# ST_LINK_V2.net
KiCad netlist of a schematic drawn in Altium Designer
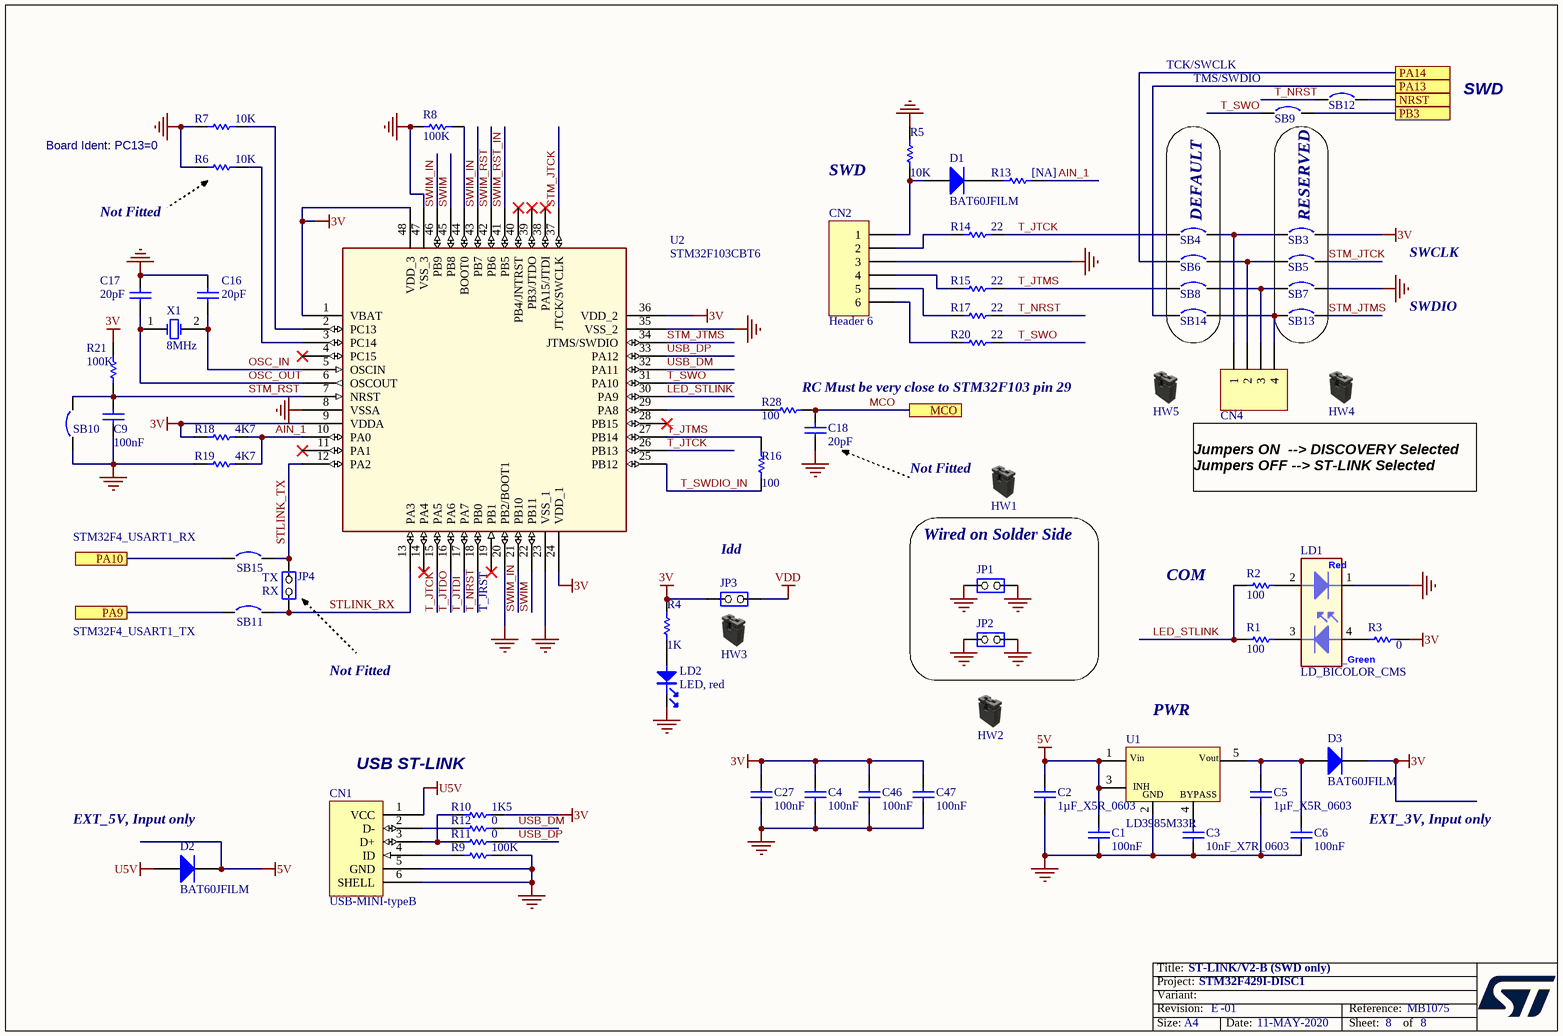
[diagram p0: ST_LINK_V2.SCHDOC]

(export (version "E")
  (design (tool "Eeschema 10.0.6"))
  (components
    (comp (ref "C1")
      (value "100nF")
      (footprint "0402C")
      (description "Capacitor 0402 / 0603 / 0805")
      (libsource (lib "MCD_TOOLS") (part "Capacitor_ST"))
    )
    (comp (ref "C2")
      (value "1µF_X5R_0603")
      (footprint "0603C")
      (description "0603  X5R 1µF")
      (fields (field (name "TOLERANCE") "10%"))
      (libsource (lib "MB963_1") (part "CAP SMD 0603  X5R 1µF 25V 10%"))
    )
    (comp (ref "C3")
      (value "10nF_X7R_0603")
      (footprint "0603C")
      (description "0603  X7R 10NF")
      (fields (field (name "TOLERANCE") "10%"))
      (libsource (lib "MB963_1") (part "CAP SMD 0603  X7R 10000PF 50V 10%"))
    )
    (comp (ref "C4")
      (value "100nF")
      (footprint "0402C")
      (description "Capacitor 0402 / 0603 / 0805")
      (libsource (lib "MCD_TOOLS") (part "Capacitor_ST"))
    )
    (comp (ref "C5")
      (value "1µF_X5R_0603")
      (footprint "0603C")
      (description "0603  X5R 1µF")
      (fields (field (name "TOLERANCE") "10%"))
      (libsource (lib "MB963_1") (part "CAP SMD 0603  X5R 1µF 25V 10%"))
    )
    (comp (ref "C6")
      (value "100nF")
      (footprint "0402C")
      (description "Capacitor 0402 / 0603 / 0805")
      (libsource (lib "MCD_TOOLS") (part "Capacitor_ST"))
    )
    (comp (ref "C9")
      (value "100nF")
      (footprint "0402C")
      (description "Capacitor 0402 / 0603 / 0805")
      (libsource (lib "MCD_TOOLS") (part "Capacitor_ST"))
    )
    (comp (ref "C16")
      (value "20pF")
      (footprint "0402C")
      (description "Capacitor 0402 / 0603 / 0805")
      (libsource (lib "MCD_TOOLS") (part "Capacitor_ST"))
    )
    (comp (ref "C17")
      (value "20pF")
      (footprint "0402C")
      (description "Capacitor 0402 / 0603 / 0805")
      (libsource (lib "MCD_TOOLS") (part "Capacitor_ST"))
    )
    (comp (ref "C18")
      (value "20pF")
      (footprint "0402C")
      (description "Capacitor 0402 / 0603 / 0805")
      (libsource (lib "MCD_TOOLS") (part "Capacitor_ST"))
    )
    (comp (ref "C27")
      (value "100nF")
      (footprint "0402C")
      (description "Capacitor 0402 / 0603 / 0805")
      (libsource (lib "MCD_TOOLS") (part "Capacitor_ST"))
    )
    (comp (ref "C46")
      (value "100nF")
      (footprint "0402C")
      (description "Capacitor 0402 / 0603 / 0805")
      (libsource (lib "MCD_TOOLS") (part "Capacitor_ST"))
    )
    (comp (ref "C47")
      (value "100nF")
      (footprint "0402C")
      (description "Capacitor 0402 / 0603 / 0805")
      (libsource (lib "MCD_TOOLS") (part "Capacitor_ST"))
    )
    (comp (ref "CN1")
      (value "USB-MINI-typeB")
      (footprint "USB-MINI-B-SMD")
      (description "USB-MINI-typeB connector")
      (libsource (lib "MCD_TOOLS") (part "USB-MINI-typeB connector"))
    )
    (comp (ref "CN2")
      (value "Header 6")
      (footprint "HDR1X6")
      (description "Header, 6-Pin")
      (fields (field (name "PUBLISHER") "Altium Limited"))
      (libsource (lib "Miscellaneous Connectors") (part "Header 6"))
    )
    (comp (ref "CN4")
      (value "Header 4")
      (footprint "Header 4")
      (description "Header, 4-Pin")
      (fields (field (name "PUBLISHER") "Altium Limited"))
      (libsource (lib "MB963_1") (part "Header 4"))
    )
    (comp (ref "D1")
      (value "BAT60JFILM")
      (footprint "SOD323/A")
      (libsource (lib "MCD_TOOLS") (part "BAT60JFILM"))
    )
    (comp (ref "D2")
      (value "BAT60JFILM")
      (footprint "SOD323/A")
      (libsource (lib "MCD_TOOLS") (part "BAT60JFILM"))
    )
    (comp (ref "D3")
      (value "BAT60JFILM")
      (footprint "SOD323/A")
      (libsource (lib "MCD_TOOLS") (part "BAT60JFILM"))
    )
    (comp (ref "HW1") (value "Shunt Black 2.54mm") (libsource (lib "MB1075") (part "Shunt Black 2.54mm")))
    (comp (ref "HW2") (value "Shunt Black 2.54mm") (libsource (lib "MB1075") (part "Shunt Black 2.54mm")))
    (comp (ref "HW3") (value "Shunt Black 2.54mm") (libsource (lib "MB1075") (part "Shunt Black 2.54mm")))
    (comp (ref "HW4") (value "Shunt Black 2.54mm") (libsource (lib "MB1075") (part "Shunt Black 2.54mm")))
    (comp (ref "HW5") (value "Shunt Black 2.54mm") (libsource (lib "MB1075") (part "Shunt Black 2.54mm")))
    (comp (ref "JP1") (value "~") (footprint "SIP2/2.54") (libsource (lib "*") (part "JP2")))
    (comp (ref "JP2") (value "~") (footprint "SIP2/2.54") (libsource (lib "*") (part "JP2")))
    (comp (ref "JP3") (value "~") (footprint "SIP2/2.54") (libsource (lib "*") (part "JP2")))
    (comp (ref "JP4") (value "JP2") (footprint "SIP2/2.54") (libsource (lib "MCD_TOOLS") (part "JP2")))
    (comp (ref "LD1")
      (value "LD_BICOLOR_CMS")
      (footprint "HSMF-A201")
      (description "Bicolor Led")
      (libsource (lib "MCD_TOOLS") (part "LD_BICOLOR_CMS"))
    )
    (comp (ref "LD2")
      (value "LED, red")
      (footprint "0603D")
      (description "LED, red, 0603")
      (libsource (lib "MCD_TOOLS") (part "LED_red"))
    )
    (comp (ref "R1")
      (value "100")
      (footprint "0402R")
      (description "Resistor 0402 / 0603 / 0805")
      (libsource (lib "MCD_TOOLS") (part "Resistor_ST"))
    )
    (comp (ref "R2")
      (value "100")
      (footprint "0402R")
      (description "Resistor 0402 / 0603 / 0805")
      (libsource (lib "MCD_TOOLS") (part "Resistor_ST"))
    )
    (comp (ref "R3")
      (value "0")
      (footprint "0402R")
      (description "Resistor 0402 / 0603 / 0805")
      (libsource (lib "MCD_TOOLS") (part "Resistor_ST"))
    )
    (comp (ref "R4")
      (value "1K")
      (footprint "0402R")
      (description "Resistor 0402 / 0603 / 0805")
      (libsource (lib "MCD_TOOLS") (part "Resistor_ST"))
    )
    (comp (ref "R5")
      (value "10K")
      (footprint "0402R")
      (description "Resistor 0402 / 0603 / 0805")
      (libsource (lib "MCD_TOOLS") (part "Resistor_ST"))
    )
    (comp (ref "R6")
      (value "10K")
      (footprint "0402R")
      (description "Resistor 0402 / 0603 / 0805")
      (libsource (lib "MCD_TOOLS") (part "Resistor_ST"))
    )
    (comp (ref "R7")
      (value "10K")
      (footprint "0402R")
      (description "Resistor 0402 / 0603 / 0805")
      (libsource (lib "MCD_TOOLS") (part "Resistor_ST"))
    )
    (comp (ref "R8")
      (value "100K")
      (footprint "0402R")
      (description "Resistor 0402 / 0603 / 0805")
      (libsource (lib "MCD_TOOLS") (part "Resistor_ST"))
    )
    (comp (ref "R9")
      (value "100K")
      (footprint "0402R")
      (description "Resistor 0402 / 0603 / 0805")
      (libsource (lib "MCD_TOOLS") (part "Resistor_ST"))
    )
    (comp (ref "R10")
      (value "1K5")
      (footprint "0402R")
      (description "Resistor 0402 / 0603 / 0805")
      (libsource (lib "MCD_TOOLS") (part "Resistor_ST"))
    )
    (comp (ref "R11")
      (value "0")
      (footprint "0402R")
      (description "Resistor 0402 / 0603 / 0805")
      (libsource (lib "MCD_TOOLS") (part "Resistor_ST"))
    )
    (comp (ref "R12")
      (value "0")
      (footprint "0402R")
      (description "Resistor 0402 / 0603 / 0805")
      (libsource (lib "MCD_TOOLS") (part "Resistor_ST"))
    )
    (comp (ref "R13")
      (value "[NA]")
      (footprint "0402R")
      (description "Resistor 0402 / 0603 / 0805")
      (libsource (lib "MCD_TOOLS") (part "Resistor_ST"))
    )
    (comp (ref "R14")
      (value "22")
      (footprint "0402R")
      (description "Resistor 0402 / 0603 / 0805")
      (libsource (lib "MCD_TOOLS") (part "Resistor_ST"))
    )
    (comp (ref "R15")
      (value "22")
      (footprint "0402R")
      (description "Resistor 0402 / 0603 / 0805")
      (libsource (lib "MCD_TOOLS") (part "Resistor_ST"))
    )
    (comp (ref "R16")
      (value "100")
      (footprint "0402R")
      (description "Resistor 0402 / 0603 / 0805")
      (libsource (lib "MCD_TOOLS") (part "Resistor_ST"))
    )
    (comp (ref "R17")
      (value "22")
      (footprint "0402R")
      (description "Resistor 0402 / 0603 / 0805")
      (libsource (lib "MCD_TOOLS") (part "Resistor_ST"))
    )
    (comp (ref "R18")
      (value "4K7")
      (footprint "0402R")
      (description "Resistor 0402 / 0603 / 0805")
      (libsource (lib "MCD_TOOLS") (part "Resistor_ST"))
    )
    (comp (ref "R19")
      (value "4K7")
      (footprint "0402R")
      (description "Resistor 0402 / 0603 / 0805")
      (libsource (lib "MCD_TOOLS") (part "Resistor_ST"))
    )
    (comp (ref "R20")
      (value "22")
      (footprint "0402R")
      (description "Resistor 0402 / 0603 / 0805")
      (libsource (lib "MCD_TOOLS") (part "Resistor_ST"))
    )
    (comp (ref "R21")
      (value "100K")
      (footprint "0402R")
      (description "Resistor 0402 / 0603 / 0805")
      (libsource (lib "MCD_TOOLS") (part "Resistor_ST"))
    )
    (comp (ref "R28")
      (value "100")
      (footprint "0402R")
      (description "Resistor 0402 / 0603 / 0805")
      (libsource (lib "MCD_TOOLS") (part "Resistor_ST"))
    )
    (comp (ref "SB3")
      (value "Circuit Breaker")
      (footprint "JP2_SMD")
      (fields (field (name "PUBLISHER") "Altium Limited"))
      (libsource (lib "MB915") (part "Circuit Breaker"))
    )
    (comp (ref "SB4")
      (value "Circuit Breaker")
      (footprint "JP2_SMD")
      (fields (field (name "PUBLISHER") "Altium Limited"))
      (libsource (lib "MB915") (part "Circuit Breaker"))
    )
    (comp (ref "SB5")
      (value "Circuit Breaker")
      (footprint "JP2_SMD")
      (fields (field (name "PUBLISHER") "Altium Limited"))
      (libsource (lib "MB915") (part "Circuit Breaker"))
    )
    (comp (ref "SB6")
      (value "Circuit Breaker")
      (footprint "JP2_SMD")
      (fields (field (name "PUBLISHER") "Altium Limited"))
      (libsource (lib "MB915") (part "Circuit Breaker"))
    )
    (comp (ref "SB7")
      (value "Circuit Breaker")
      (footprint "JP2_SMD")
      (fields (field (name "PUBLISHER") "Altium Limited"))
      (libsource (lib "MB915") (part "Circuit Breaker"))
    )
    (comp (ref "SB8")
      (value "Circuit Breaker")
      (footprint "JP2_SMD")
      (fields (field (name "PUBLISHER") "Altium Limited"))
      (libsource (lib "MB915") (part "Circuit Breaker"))
    )
    (comp (ref "SB9")
      (value "Circuit Breaker")
      (footprint "JP2_SMD")
      (fields (field (name "PUBLISHER") "Altium Limited"))
      (libsource (lib "MCD_TOOLS") (part "Circuit Breaker"))
    )
    (comp (ref "SB10")
      (value "Circuit Breaker")
      (footprint "JP2_SMD")
      (fields (field (name "PUBLISHER") "Altium Limited"))
      (libsource (lib "MB915") (part "Circuit Breaker"))
    )
    (comp (ref "SB11")
      (value "Circuit Breaker")
      (footprint "JP2_SMD")
      (fields (field (name "PUBLISHER") "Altium Limited"))
      (libsource (lib "MCD_TOOLS") (part "Circuit Breaker"))
    )
    (comp (ref "SB12")
      (value "Circuit Breaker")
      (footprint "JP2_SMD")
      (fields (field (name "PUBLISHER") "Altium Limited"))
      (libsource (lib "MB915") (part "Circuit Breaker"))
    )
    (comp (ref "SB13")
      (value "Circuit Breaker")
      (footprint "JP2_SMD")
      (fields (field (name "PUBLISHER") "Altium Limited"))
      (libsource (lib "MB915") (part "Circuit Breaker"))
    )
    (comp (ref "SB14")
      (value "Circuit Breaker")
      (footprint "JP2_SMD")
      (fields (field (name "PUBLISHER") "Altium Limited"))
      (libsource (lib "MB915") (part "Circuit Breaker"))
    )
    (comp (ref "SB15")
      (value "Circuit Breaker")
      (footprint "JP2_SMD")
      (fields (field (name "PUBLISHER") "Altium Limited"))
      (libsource (lib "MCD_TOOLS") (part "Circuit Breaker"))
    )
    (comp (ref "U1")
      (value "LD3985M33R")
      (footprint "SOT-23-5L")
      (description "Ultra low drop-low noise BiCMOS voltage, regulators low ESR capacitors compatible")
      (libsource (lib "MCD_TOOLS") (part "LD3985M33R"))
    )
    (comp (ref "U2")
      (value "STM32F103CBT6")
      (footprint "QFP48 7x7")
      (description "Medium-density performance line ARM-based 32-bit MCU with 128KB Flash")
      (libsource (lib "MCD_TOOLS") (part "STM32F103CBT6"))
    )
    (comp (ref "X1")
      (value "8MHz")
      (footprint "XTAL1")
      (description "Crystal Oscillator,8Mhz,20PF,20PPM,-10-70 degree,DIP,HC-49S")
      (libsource (lib "MCD_TOOLS") (part "XTAL"))
    )
  )
  (nets
    (net (code "1") (name "/AIN_1") (class "Default")
      (node (ref "R13") (pin "2") (pinfunction "2_2") (pintype "passive"))
      (node (ref "R18") (pin "2") (pinfunction "2_2") (pintype "passive"))
      (node (ref "R19") (pin "2") (pinfunction "2_2") (pintype "passive"))
      (node (ref "U2") (pin "10") (pinfunction "PA0_10") (pintype "bidirectional"))
    )
    (net (code "2") (name "/LED_STLINK") (class "Default")
      (node (ref "R1") (pin "1") (pinfunction "1_1") (pintype "passive"))
      (node (ref "R2") (pin "1") (pinfunction "1_1") (pintype "passive"))
      (node (ref "U2") (pin "30") (pinfunction "PA9_30") (pintype "bidirectional"))
    )
    (net (code "3") (name "/MCO") (class "Default")
      (node (ref "C18") (pin "2") (pinfunction "2_2") (pintype "passive"))
      (node (ref "R28") (pin "2") (pinfunction "2_2") (pintype "passive"))
    )
    (net (code "4") (name "/NRST") (class "Default")
      (node (ref "SB12") (pin "2") (pinfunction "2_2") (pintype "passive"))
    )
    (net (code "5") (name "/OSC_IN") (class "Default")
      (node (ref "C16") (pin "1") (pinfunction "1_1") (pintype "passive"))
      (node (ref "U2") (pin "5") (pinfunction "OSCIN_5") (pintype "input"))
      (node (ref "X1") (pin "2") (pinfunction "OSC2_2") (pintype "passive"))
    )
    (net (code "6") (name "/OSC_OUT") (class "Default")
      (node (ref "C17") (pin "1") (pinfunction "1_1") (pintype "passive"))
      (node (ref "U2") (pin "6") (pinfunction "OSCOUT_6") (pintype "output"))
      (node (ref "X1") (pin "1") (pinfunction "OSC1_1") (pintype "passive"))
    )
    (net (code "7") (name "/PA9") (class "Default")
      (node (ref "SB11") (pin "1") (pinfunction "1_1") (pintype "passive"))
    )
    (net (code "8") (name "/PA10") (class "Default")
      (node (ref "SB15") (pin "1") (pinfunction "1_1") (pintype "passive"))
    )
    (net (code "9") (name "/PA13") (class "Default")
      (node (ref "SB14") (pin "1") (pinfunction "1_1") (pintype "passive"))
    )
    (net (code "10") (name "/PA14") (class "Default")
      (node (ref "SB6") (pin "1") (pinfunction "1_1") (pintype "passive"))
    )
    (net (code "11") (name "/PB3") (class "Default")
      (node (ref "SB9") (pin "2") (pinfunction "2_2") (pintype "passive"))
    )
    (net (code "12") (name "/STLINK_RX") (class "Default")
      (node (ref "JP4") (pin "1") (pinfunction "COMMON_1") (pintype "passive"))
      (node (ref "SB11") (pin "2") (pinfunction "2_2") (pintype "passive"))
      (node (ref "U2") (pin "13") (pinfunction "PA3_13") (pintype "bidirectional"))
    )
    (net (code "13") (name "/STLINK_TX") (class "Default")
      (node (ref "JP4") (pin "2") (pinfunction "NO_2") (pintype "passive"))
      (node (ref "SB15") (pin "2") (pinfunction "2_2") (pintype "passive"))
      (node (ref "U2") (pin "12") (pinfunction "PA2_12") (pintype "bidirectional"))
    )
    (net (code "14") (name "/STM_JTCK") (class "Default")
      (node (ref "SB5") (pin "2") (pinfunction "2_2") (pintype "passive"))
      (node (ref "U2") (pin "37") (pinfunction "JTCK/SWCLK_37") (pintype "bidirectional"))
    )
    (net (code "15") (name "/STM_JTMS") (class "Default")
      (node (ref "SB13") (pin "2") (pinfunction "2_2") (pintype "passive"))
      (node (ref "U2") (pin "34") (pinfunction "JTMS/SWDIO_34") (pintype "bidirectional"))
    )
    (net (code "16") (name "/STM_RST") (class "Default")
      (node (ref "C9") (pin "2") (pinfunction "2_2") (pintype "passive"))
      (node (ref "R21") (pin "1") (pinfunction "1_1") (pintype "passive"))
      (node (ref "SB10") (pin "2") (pinfunction "2_2") (pintype "passive"))
      (node (ref "U2") (pin "7") (pinfunction "NRST_7") (pintype "input"))
    )
    (net (code "17") (name "/SWIM") (class "Default")
      (node (ref "U2") (pin "22") (pinfunction "PB11_22") (pintype "bidirectional"))
      (node (ref "U2") (pin "45") (pinfunction "PB8_45") (pintype "bidirectional"))
    )
    (net (code "18") (name "/SWIM_IN") (class "Default")
      (node (ref "U2") (pin "21") (pinfunction "PB10_21") (pintype "bidirectional"))
      (node (ref "U2") (pin "43") (pinfunction "PB7_43") (pintype "bidirectional"))
      (node (ref "U2") (pin "46") (pinfunction "PB9_46") (pintype "bidirectional"))
    )
    (net (code "19") (name "/SWIM_RST") (class "Default")
      (node (ref "U2") (pin "42") (pinfunction "PB6_42") (pintype "bidirectional"))
    )
    (net (code "20") (name "/SWIM_RST_IN") (class "Default")
      (node (ref "U2") (pin "41") (pinfunction "PB5_41") (pintype "bidirectional"))
    )
    (net (code "21") (name "/T_JTCK") (class "Default")
      (node (ref "R14") (pin "2") (pinfunction "2_2") (pintype "passive"))
      (node (ref "SB4") (pin "1") (pinfunction "1_1") (pintype "passive"))
      (node (ref "U2") (pin "15") (pinfunction "PA5_15") (pintype "bidirectional"))
      (node (ref "U2") (pin "26") (pinfunction "PB13_26") (pintype "bidirectional"))
    )
    (net (code "22") (name "/T_JTDI") (class "Default")
      (node (ref "U2") (pin "17") (pinfunction "PA7_17") (pintype "bidirectional"))
    )
    (net (code "23") (name "/T_JTDO") (class "Default")
      (node (ref "U2") (pin "16") (pinfunction "PA6_16") (pintype "bidirectional"))
    )
    (net (code "24") (name "/T_JTMS") (class "Default")
      (node (ref "R15") (pin "2") (pinfunction "2_2") (pintype "passive"))
      (node (ref "R16") (pin "2") (pinfunction "2_2") (pintype "passive"))
      (node (ref "SB8") (pin "1") (pinfunction "1_1") (pintype "passive"))
      (node (ref "U2") (pin "27") (pinfunction "PB14_27") (pintype "bidirectional"))
    )
    (net (code "25") (name "/T_NRST") (class "Default")
      (node (ref "R17") (pin "2") (pinfunction "2_2") (pintype "passive"))
      (node (ref "SB12") (pin "1") (pinfunction "1_1") (pintype "passive"))
      (node (ref "U2") (pin "18") (pinfunction "PB0_18") (pintype "bidirectional"))
    )
    (net (code "26") (name "/T_SWDIO_IN") (class "Default")
      (node (ref "R16") (pin "1") (pinfunction "1_1") (pintype "passive"))
      (node (ref "U2") (pin "25") (pinfunction "PB12_25") (pintype "bidirectional"))
    )
    (net (code "27") (name "/T_SWO") (class "Default")
      (node (ref "R20") (pin "2") (pinfunction "2_2") (pintype "passive"))
      (node (ref "SB9") (pin "1") (pinfunction "1_1") (pintype "passive"))
      (node (ref "U2") (pin "31") (pinfunction "PA10_31") (pintype "bidirectional"))
    )
    (net (code "28") (name "/USB_DM") (class "Default")
      (node (ref "R12") (pin "2") (pinfunction "2_2") (pintype "passive"))
      (node (ref "U2") (pin "32") (pinfunction "PA11_32") (pintype "bidirectional"))
    )
    (net (code "29") (name "/USB_DP") (class "Default")
      (node (ref "R11") (pin "2") (pinfunction "2_2") (pintype "passive"))
      (node (ref "U2") (pin "33") (pinfunction "PA12_33") (pintype "bidirectional"))
    )
    (net (code "30") (name "3V") (class "Default")
      (node (ref "C27") (pin "2") (pinfunction "2_2") (pintype "passive"))
      (node (ref "C4") (pin "2") (pinfunction "2_2") (pintype "passive"))
      (node (ref "C46") (pin "2") (pinfunction "2_2") (pintype "passive"))
      (node (ref "C47") (pin "2") (pinfunction "2_2") (pintype "passive"))
      (node (ref "D3") (pin "2") (pinfunction "K_2") (pintype "passive"))
      (node (ref "JP3") (pin "1") (pinfunction "COMMON_1") (pintype "passive"))
      (node (ref "R10") (pin "2") (pinfunction "2_2") (pintype "passive"))
      (node (ref "R18") (pin "1") (pinfunction "1_1") (pintype "passive"))
      (node (ref "R21") (pin "2") (pinfunction "2_2") (pintype "passive"))
      (node (ref "R3") (pin "2") (pinfunction "2_2") (pintype "passive"))
      (node (ref "R4") (pin "2") (pinfunction "2_2") (pintype "passive"))
      (node (ref "SB3") (pin "2") (pinfunction "2_2") (pintype "passive"))
      (node (ref "U2") (pin "1") (pinfunction "VBAT_1") (pintype "power_in"))
      (node (ref "U2") (pin "24") (pinfunction "VDD_1_24") (pintype "power_in"))
      (node (ref "U2") (pin "36") (pinfunction "VDD_2_36") (pintype "power_in"))
      (node (ref "U2") (pin "48") (pinfunction "VDD_3_48") (pintype "power_in"))
      (node (ref "U2") (pin "9") (pinfunction "VDDA_9") (pintype "power_in"))
    )
    (net (code "31") (name "5V") (class "Default")
      (node (ref "C1") (pin "2") (pinfunction "2_2") (pintype "passive"))
      (node (ref "C2") (pin "2") (pinfunction "2_2") (pintype "passive"))
      (node (ref "D2") (pin "2") (pinfunction "K_2") (pintype "passive"))
      (node (ref "U1") (pin "1") (pinfunction "Vin_1") (pintype "passive"))
      (node (ref "U1") (pin "3") (pinfunction "CE_3") (pintype "passive"))
    )
    (net (code "32") (name "GND") (class "Default")
      (node (ref "C1") (pin "1") (pinfunction "1_1") (pintype "passive"))
      (node (ref "C16") (pin "2") (pinfunction "2_2") (pintype "passive"))
      (node (ref "C17") (pin "2") (pinfunction "2_2") (pintype "passive"))
      (node (ref "C18") (pin "1") (pinfunction "1_1") (pintype "passive"))
      (node (ref "C2") (pin "1") (pinfunction "1_1") (pintype "passive"))
      (node (ref "C27") (pin "1") (pinfunction "1_1") (pintype "passive"))
      (node (ref "C3") (pin "1") (pinfunction "1_1") (pintype "passive"))
      (node (ref "C4") (pin "1") (pinfunction "1_1") (pintype "passive"))
      (node (ref "C46") (pin "1") (pinfunction "1_1") (pintype "passive"))
      (node (ref "C47") (pin "1") (pinfunction "1_1") (pintype "passive"))
      (node (ref "C5") (pin "2") (pinfunction "2_2") (pintype "passive"))
      (node (ref "C6") (pin "1") (pinfunction "1_1") (pintype "passive"))
      (node (ref "C9") (pin "1") (pinfunction "1_1") (pintype "passive"))
      (node (ref "CN1") (pin "5") (pinfunction "GND_5") (pintype "passive"))
      (node (ref "CN1") (pin "6") (pinfunction "SHELL_6") (pintype "passive"))
      (node (ref "CN2") (pin "3") (pinfunction "3_3") (pintype "passive"))
      (node (ref "JP1") (pin "1") (pinfunction "COMMON_1") (pintype "passive"))
      (node (ref "JP1") (pin "2") (pinfunction "NO_2") (pintype "passive"))
      (node (ref "JP2") (pin "1") (pinfunction "COMMON_1") (pintype "passive"))
      (node (ref "JP2") (pin "2") (pinfunction "NO_2") (pintype "passive"))
      (node (ref "LD1") (pin "1") (pinfunction "1_1") (pintype "passive"))
      (node (ref "LD2") (pin "2") (pintype "passive"))
      (node (ref "R19") (pin "1") (pinfunction "1_1") (pintype "passive"))
      (node (ref "R5") (pin "2") (pinfunction "2_2") (pintype "passive"))
      (node (ref "R6") (pin "1") (pinfunction "1_1") (pintype "passive"))
      (node (ref "R7") (pin "1") (pinfunction "1_1") (pintype "passive"))
      (node (ref "R8") (pin "1") (pinfunction "1_1") (pintype "passive"))
      (node (ref "R9") (pin "2") (pinfunction "2_2") (pintype "passive"))
      (node (ref "SB10") (pin "1") (pinfunction "1_1") (pintype "passive"))
      (node (ref "SB7") (pin "2") (pinfunction "2_2") (pintype "passive"))
      (node (ref "U1") (pin "2") (pinfunction "GND_2") (pintype "passive"))
      (node (ref "U2") (pin "20") (pinfunction "PB2/BOOT1_20") (pintype "bidirectional"))
      (node (ref "U2") (pin "23") (pinfunction "VSS_1_23") (pintype "power_in"))
      (node (ref "U2") (pin "35") (pinfunction "VSS_2_35") (pintype "power_in"))
      (node (ref "U2") (pin "47") (pinfunction "VSS_3_47") (pintype "power_in"))
      (node (ref "U2") (pin "8") (pinfunction "VSSA_8") (pintype "power_in"))
    )
    (net (code "33") (name "Net-(CN1-D+)") (class "Default")
      (node (ref "CN1") (pin "3") (pinfunction "D+_3") (pintype "bidirectional"))
      (node (ref "R10") (pin "1") (pinfunction "1_1") (pintype "passive"))
      (node (ref "R11") (pin "1") (pinfunction "1_1") (pintype "passive"))
    )
    (net (code "34") (name "Net-(CN1-D-)") (class "Default")
      (node (ref "CN1") (pin "2") (pinfunction "D-_2") (pintype "bidirectional"))
      (node (ref "R12") (pin "1") (pinfunction "1_1") (pintype "passive"))
    )
    (net (code "35") (name "Net-(CN1-ID)") (class "Default")
      (node (ref "CN1") (pin "4") (pinfunction "ID_4") (pintype "input"))
      (node (ref "R9") (pin "1") (pinfunction "1_1") (pintype "passive"))
    )
    (net (code "36") (name "Net-(CN2-Pad2)") (class "Default")
      (node (ref "CN2") (pin "2") (pinfunction "2_2") (pintype "passive"))
      (node (ref "R14") (pin "1") (pinfunction "1_1") (pintype "passive"))
    )
    (net (code "37") (name "Net-(CN2-Pad4)") (class "Default")
      (node (ref "CN2") (pin "4") (pinfunction "4_4") (pintype "passive"))
      (node (ref "R15") (pin "1") (pinfunction "1_1") (pintype "passive"))
    )
    (net (code "38") (name "Net-(CN2-Pad5)") (class "Default")
      (node (ref "CN2") (pin "5") (pinfunction "5_5") (pintype "passive"))
      (node (ref "R17") (pin "1") (pinfunction "1_1") (pintype "passive"))
    )
    (net (code "39") (name "Net-(CN2-Pad6)") (class "Default")
      (node (ref "CN2") (pin "6") (pinfunction "6_6") (pintype "passive"))
      (node (ref "R20") (pin "1") (pinfunction "1_1") (pintype "passive"))
    )
    (net (code "40") (name "Net-(CN4-Pad1)") (class "Default")
      (node (ref "CN4") (pin "1") (pinfunction "1_1") (pintype "passive"))
      (node (ref "SB3") (pin "1") (pinfunction "1_1") (pintype "passive"))
      (node (ref "SB4") (pin "2") (pinfunction "2_2") (pintype "passive"))
    )
    (net (code "41") (name "Net-(CN4-Pad2)") (class "Default")
      (node (ref "CN4") (pin "2") (pinfunction "2_2") (pintype "passive"))
      (node (ref "SB5") (pin "1") (pinfunction "1_1") (pintype "passive"))
      (node (ref "SB6") (pin "2") (pinfunction "2_2") (pintype "passive"))
    )
    (net (code "42") (name "Net-(CN4-Pad3)") (class "Default")
      (node (ref "CN4") (pin "3") (pinfunction "3_3") (pintype "passive"))
      (node (ref "SB7") (pin "1") (pinfunction "1_1") (pintype "passive"))
      (node (ref "SB8") (pin "2") (pinfunction "2_2") (pintype "passive"))
    )
    (net (code "43") (name "Net-(CN4-Pad4)") (class "Default")
      (node (ref "CN4") (pin "4") (pinfunction "4_4") (pintype "passive"))
      (node (ref "SB13") (pin "1") (pinfunction "1_1") (pintype "passive"))
      (node (ref "SB14") (pin "2") (pinfunction "2_2") (pintype "passive"))
    )
    (net (code "44") (name "Net-(D1-A)") (class "Default")
      (node (ref "CN2") (pin "1") (pinfunction "1_1") (pintype "passive"))
      (node (ref "D1") (pin "1") (pinfunction "A_1") (pintype "passive"))
      (node (ref "R5") (pin "1") (pinfunction "1_1") (pintype "passive"))
    )
    (net (code "45") (name "Net-(D1-K)") (class "Default")
      (node (ref "D1") (pin "2") (pinfunction "K_2") (pintype "passive"))
      (node (ref "R13") (pin "1") (pinfunction "1_1") (pintype "passive"))
    )
    (net (code "46") (name "Net-(D3-A)") (class "Default")
      (node (ref "C5") (pin "1") (pinfunction "1_1") (pintype "passive"))
      (node (ref "C6") (pin "2") (pinfunction "2_2") (pintype "passive"))
      (node (ref "D3") (pin "1") (pinfunction "A_1") (pintype "passive"))
      (node (ref "U1") (pin "5") (pinfunction "Vout_5") (pintype "passive"))
    )
    (net (code "47") (name "Net-(LD1-Pad2)") (class "Default")
      (node (ref "LD1") (pin "2") (pinfunction "2_2") (pintype "passive"))
      (node (ref "R2") (pin "2") (pinfunction "2_2") (pintype "passive"))
    )
    (net (code "48") (name "Net-(LD1-Pad3)") (class "Default")
      (node (ref "LD1") (pin "3") (pinfunction "3_3") (pintype "passive"))
      (node (ref "R1") (pin "2") (pinfunction "2_2") (pintype "passive"))
    )
    (net (code "49") (name "Net-(LD1-Pad4)") (class "Default")
      (node (ref "LD1") (pin "4") (pinfunction "4_4") (pintype "passive"))
      (node (ref "R3") (pin "1") (pinfunction "1_1") (pintype "passive"))
    )
    (net (code "50") (name "Net-(LD2-Pad1)") (class "Default")
      (node (ref "LD2") (pin "1") (pintype "passive"))
      (node (ref "R4") (pin "1") (pinfunction "1_1") (pintype "passive"))
    )
    (net (code "51") (name "Net-(U1-BYPASS)") (class "Default")
      (node (ref "C3") (pin "2") (pinfunction "2_2") (pintype "passive"))
      (node (ref "U1") (pin "4") (pinfunction "BYPASS_4") (pintype "passive"))
    )
    (net (code "52") (name "Net-(U2-BOOT0)") (class "Default")
      (node (ref "R8") (pin "2") (pinfunction "2_2") (pintype "passive"))
      (node (ref "U2") (pin "44") (pinfunction "BOOT0_44") (pintype "bidirectional"))
    )
    (net (code "53") (name "Net-(U2-PA8)") (class "Default")
      (node (ref "R28") (pin "1") (pinfunction "1_1") (pintype "passive"))
      (node (ref "U2") (pin "29") (pinfunction "PA8_29") (pintype "bidirectional"))
    )
    (net (code "54") (name "Net-(U2-PC13)") (class "Default")
      (node (ref "R7") (pin "2") (pinfunction "2_2") (pintype "passive"))
      (node (ref "U2") (pin "2") (pinfunction "PC13_2") (pintype "bidirectional"))
    )
    (net (code "55") (name "Net-(U2-PC14)") (class "Default")
      (node (ref "R6") (pin "2") (pinfunction "2_2") (pintype "passive"))
      (node (ref "U2") (pin "3") (pinfunction "PC14_3") (pintype "bidirectional"))
    )
    (net (code "56") (name "U5V") (class "Default")
      (node (ref "CN1") (pin "1") (pinfunction "VCC_1") (pintype "power_in"))
      (node (ref "D2") (pin "1") (pinfunction "A_1") (pintype "passive"))
    )
    (net (code "57") (name "VDD") (class "Default")
      (node (ref "JP3") (pin "2") (pinfunction "NO_2") (pintype "passive"))
    )
    (net (code "58") (name "unconnected-(U2-PA1-Pad11)") (class "Default")
      (node (ref "U2") (pin "11") (pinfunction "PA1_11") (pintype "bidirectional+no_connect"))
    )
    (net (code "59") (name "unconnected-(U2-PA4-Pad14)") (class "Default")
      (node (ref "U2") (pin "14") (pinfunction "PA4_14") (pintype "bidirectional+no_connect"))
    )
    (net (code "60") (name "unconnected-(U2-PA15{slash}JTDI-Pad38)") (class "Default")
      (node (ref "U2") (pin "38") (pinfunction "PA15/JTDI_38") (pintype "bidirectional+no_connect"))
    )
    (net (code "61") (name "unconnected-(U2-PB1-Pad19)") (class "Default")
      (node (ref "U2") (pin "19") (pinfunction "PB1_19") (pintype "input+no_connect"))
    )
    (net (code "62") (name "unconnected-(U2-PB3{slash}JTDO-Pad39)") (class "Default")
      (node (ref "U2") (pin "39") (pinfunction "PB3/JTDO_39") (pintype "bidirectional+no_connect"))
    )
    (net (code "63") (name "unconnected-(U2-PB4{slash}JNTRST-Pad40)") (class "Default")
      (node (ref "U2") (pin "40") (pinfunction "PB4/JNTRST_40") (pintype "bidirectional+no_connect"))
    )
    (net (code "64") (name "unconnected-(U2-PB15-Pad28)") (class "Default")
      (node (ref "U2") (pin "28") (pinfunction "PB15_28") (pintype "bidirectional+no_connect"))
    )
    (net (code "65") (name "unconnected-(U2-PC15-Pad4)") (class "Default")
      (node (ref "U2") (pin "4") (pinfunction "PC15_4") (pintype "bidirectional+no_connect"))
    )
  )
)
